# Main_Schematic.net
KiCad netlist of a schematic drawn in Altium Designer
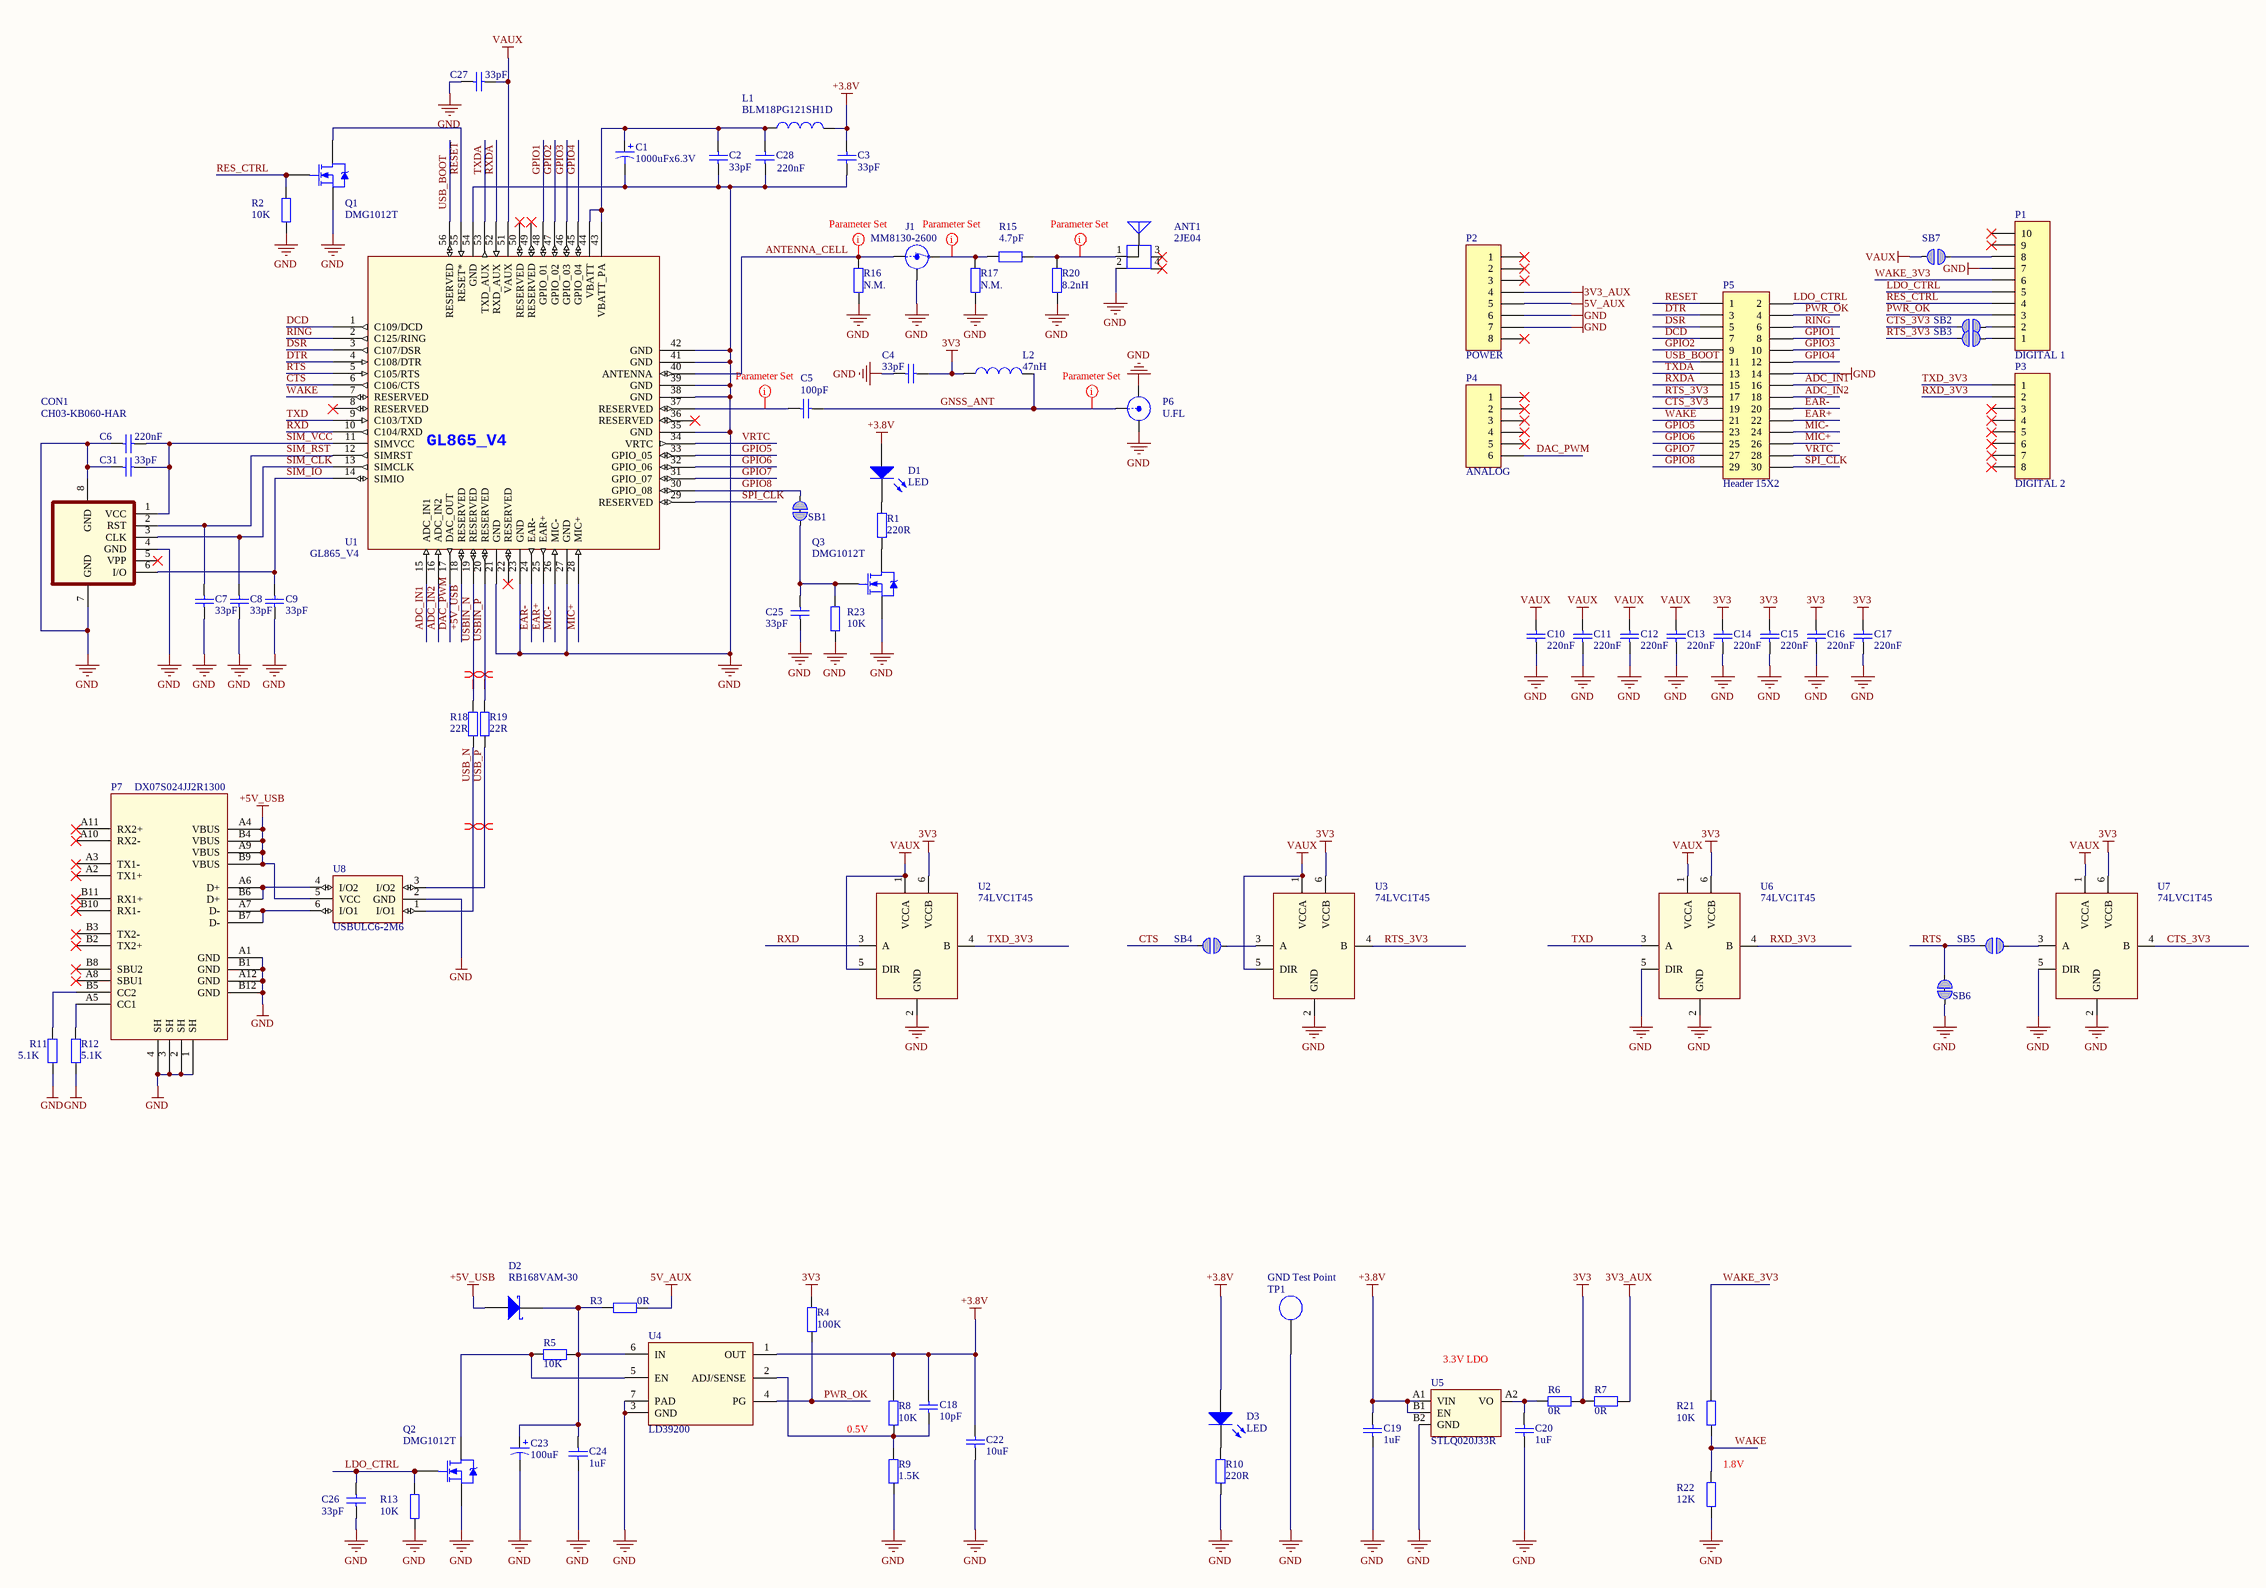
[diagram p0: Main Schematic.SchDoc]

(export (version "E")
  (design (tool "Eeschema 10.0.6"))
  (components
    (comp (ref "ANT1")
      (value "2JE04")
      (footprint "2JE04")
      (description "Generic Antenna")
      (fields (field (name "MANUFACTURER") "2J"))
      (libsource (lib "RUT_GE310_GNSS") (part "Antenna"))
    )
    (comp (ref "C1")
      (value "1000uFx6.3V")
      (footprint "7361-38")
      (fields
        (field (name "MANUFACTURER") "AVX")
        (field (name "MANUFACTURER PART NO.") "TPSV108M006R0050")
        (field (name "Comment") "electrolytic capacitor")
      )
      (libsource (lib "Miscellaneous Devices") (part "Cap Pol1"))
    )
    (comp (ref "C2")
      (value "33pF")
      (footprint "C0402")
      (description "Capacitor (Semiconductor SIM Model)")
      (fields (field (name "MANUFACTURER") "AVX") (field (name "MANUFACTURER PART NO.") "04025A330JAT2A"))
      (libsource (lib "Miscellaneous Devices") (part "Cap Semi"))
    )
    (comp (ref "C3")
      (value "33pF")
      (footprint "C0402")
      (description "Capacitor (Semiconductor SIM Model)")
      (fields (field (name "MANUFACTURER") "AVX") (field (name "MANUFACTURER PART NO.") "04025A330JAT2A"))
      (libsource (lib "Miscellaneous Devices") (part "Cap Semi"))
    )
    (comp (ref "C4")
      (value "33pF")
      (footprint "C0402")
      (description "Capacitor (Semiconductor SIM Model)")
      (fields (field (name "MANUFACTURER") "AVX") (field (name "MANUFACTURER PART NO.") "04025A330JAT2A"))
      (libsource (lib "Miscellaneous Devices") (part "Cap Semi"))
    )
    (comp (ref "C5")
      (value "100pF")
      (footprint "C0402")
      (description "Capacitor (Semiconductor SIM Model)")
      (fields
        (field (name "MANUFACTURER") "Samsung Electronics")
        (field (name "MANUFACTURER PART NO.") "CL05C101JB5NNNC")
      )
      (libsource (lib "Miscellaneous Devices") (part "Cap Semi"))
    )
    (comp (ref "C6")
      (value "220nF")
      (footprint "C0402")
      (description "Capacitor (Semiconductor SIM Model)")
      (fields
        (field (name "MANUFACTURER") "YAGEO")
        (field (name "MANUFACTURER PART NO.") "CC0402KRX5R5BB224")
      )
      (libsource (lib "Miscellaneous Devices") (part "Cap Semi"))
    )
    (comp (ref "C7")
      (value "33pF")
      (footprint "C0402")
      (description "Capacitor (Semiconductor SIM Model)")
      (fields (field (name "MANUFACTURER") "AVX") (field (name "MANUFACTURER PART NO.") "04025A330JAT2A"))
      (libsource (lib "Miscellaneous Devices") (part "Cap Semi"))
    )
    (comp (ref "C8")
      (value "33pF")
      (footprint "C0402")
      (description "Capacitor (Semiconductor SIM Model)")
      (fields (field (name "MANUFACTURER") "AVX") (field (name "MANUFACTURER PART NO.") "04025A330JAT2A"))
      (libsource (lib "Miscellaneous Devices") (part "Cap Semi"))
    )
    (comp (ref "C9")
      (value "33pF")
      (footprint "C0402")
      (description "Capacitor (Semiconductor SIM Model)")
      (fields (field (name "MANUFACTURER") "AVX") (field (name "MANUFACTURER PART NO.") "04025A330JAT2A"))
      (libsource (lib "Miscellaneous Devices") (part "Cap Semi"))
    )
    (comp (ref "C10")
      (value "220nF")
      (footprint "C0402")
      (description "Capacitor (Semiconductor SIM Model)")
      (fields
        (field (name "MANUFACTURER") "YAGEO")
        (field (name "MANUFACTURER PART NO.") "CC0402KRX5R5BB224")
      )
      (libsource (lib "Miscellaneous Devices") (part "Cap Semi"))
    )
    (comp (ref "C11")
      (value "220nF")
      (footprint "C0402")
      (description "Capacitor (Semiconductor SIM Model)")
      (fields
        (field (name "MANUFACTURER") "YAGEO")
        (field (name "MANUFACTURER PART NO.") "CC0402KRX5R5BB224")
      )
      (libsource (lib "Miscellaneous Devices") (part "Cap Semi"))
    )
    (comp (ref "C12")
      (value "220nF")
      (footprint "C0402")
      (description "Capacitor (Semiconductor SIM Model)")
      (fields
        (field (name "MANUFACTURER") "YAGEO")
        (field (name "MANUFACTURER PART NO.") "CC0402KRX5R5BB224")
      )
      (libsource (lib "Miscellaneous Devices") (part "Cap Semi"))
    )
    (comp (ref "C13")
      (value "220nF")
      (footprint "C0402")
      (description "Capacitor (Semiconductor SIM Model)")
      (fields
        (field (name "MANUFACTURER") "YAGEO")
        (field (name "MANUFACTURER PART NO.") "CC0402KRX5R5BB224")
      )
      (libsource (lib "Miscellaneous Devices") (part "Cap Semi"))
    )
    (comp (ref "C14")
      (value "220nF")
      (footprint "C0402")
      (description "Capacitor (Semiconductor SIM Model)")
      (fields
        (field (name "MANUFACTURER") "YAGEO")
        (field (name "MANUFACTURER PART NO.") "CC0402KRX5R5BB224")
      )
      (libsource (lib "Miscellaneous Devices") (part "Cap Semi"))
    )
    (comp (ref "C15")
      (value "220nF")
      (footprint "C0402")
      (description "Capacitor (Semiconductor SIM Model)")
      (fields
        (field (name "MANUFACTURER") "YAGEO")
        (field (name "MANUFACTURER PART NO.") "CC0402KRX5R5BB224")
      )
      (libsource (lib "Miscellaneous Devices") (part "Cap Semi"))
    )
    (comp (ref "C16")
      (value "220nF")
      (footprint "C0402")
      (description "Capacitor (Semiconductor SIM Model)")
      (fields
        (field (name "MANUFACTURER") "YAGEO")
        (field (name "MANUFACTURER PART NO.") "CC0402KRX5R5BB224")
      )
      (libsource (lib "Miscellaneous Devices") (part "Cap Semi"))
    )
    (comp (ref "C17")
      (value "220nF")
      (footprint "C0402")
      (description "Capacitor (Semiconductor SIM Model)")
      (fields
        (field (name "MANUFACTURER") "YAGEO")
        (field (name "MANUFACTURER PART NO.") "CC0402KRX5R5BB224")
      )
      (libsource (lib "Miscellaneous Devices") (part "Cap Semi"))
    )
    (comp (ref "C18")
      (value "10pF")
      (footprint "C0402")
      (description "Capacitor (Semiconductor SIM Model)")
      (fields
        (field (name "MANUFACTURER") "YAGEO")
        (field (name "MANUFACTURER PART NO.") "CC0402JRNPO9BN100")
      )
      (libsource (lib "Miscellaneous Devices") (part "Cap Semi"))
    )
    (comp (ref "C19")
      (value "1uF")
      (footprint "C0402")
      (description "Capacitor (Semiconductor SIM Model)")
      (fields
        (field (name "MANUFACTURER") "Samsung Electronics")
        (field (name "MANUFACTURER PART NO.") "CL05A225MQ5NNNC")
      )
      (libsource (lib "Miscellaneous Devices") (part "Cap Semi"))
    )
    (comp (ref "C20")
      (value "1uF")
      (footprint "C0402")
      (description "Capacitor (Semiconductor SIM Model)")
      (fields
        (field (name "MANUFACTURER") "Samsung Electronics")
        (field (name "MANUFACTURER PART NO.") "CL05A225MQ5NNNC")
      )
      (libsource (lib "Miscellaneous Devices") (part "Cap Semi"))
    )
    (comp (ref "C22")
      (value "10uF")
      (footprint "C0402")
      (description "Capacitor (Semiconductor SIM Model)")
      (fields
        (field (name "MANUFACTURER") "Samsung Electronics")
        (field (name "MANUFACTURER PART NO.") "CL05A106MP5NUNC")
      )
      (libsource (lib "Miscellaneous Devices") (part "Cap Semi"))
    )
    (comp (ref "C23")
      (value "100uF")
      (footprint "Case-B")
      (fields
        (field (name "MANUFACTURER") "AVX")
        (field (name "MANUFACTURER PART NO.") "TPSB107K006R0400")
        (field (name "Comment") "electrolytic capacitor")
      )
      (libsource (lib "Miscellaneous Devices") (part "Cap Pol1"))
    )
    (comp (ref "C24")
      (value "1uF")
      (footprint "C0402")
      (description "Capacitor (Semiconductor SIM Model)")
      (fields
        (field (name "MANUFACTURER") "Samsung Electronics")
        (field (name "MANUFACTURER PART NO.") "CL05A106MP5NUNC")
      )
      (libsource (lib "Miscellaneous Devices") (part "Cap Semi"))
    )
    (comp (ref "C25")
      (value "33pF")
      (footprint "C0402")
      (description "Capacitor (Semiconductor SIM Model)")
      (fields (field (name "MANUFACTURER") "AVX") (field (name "MANUFACTURER PART NO.") "04025A330JAT2A"))
      (libsource (lib "Miscellaneous Devices") (part "Cap Semi"))
    )
    (comp (ref "C26")
      (value "33pF")
      (footprint "C0402")
      (description "Capacitor (Semiconductor SIM Model)")
      (fields
        (field (name "MANUFACTURER") "YAGEO")
        (field (name "MANUFACTURER PART NO.") "CC0402JRNPO9BN100")
      )
      (libsource (lib "Miscellaneous Devices") (part "Cap Semi"))
    )
    (comp (ref "C27")
      (value "33pF")
      (footprint "C0402")
      (description "Capacitor (Semiconductor SIM Model)")
      (fields (field (name "MANUFACTURER") "AVX") (field (name "MANUFACTURER PART NO.") "04025A330JAT2A"))
      (libsource (lib "Miscellaneous Devices") (part "Cap Semi"))
    )
    (comp (ref "C28")
      (value "220nF")
      (footprint "C0402")
      (description "Capacitor (Semiconductor SIM Model)")
      (fields
        (field (name "MANUFACTURER") "YAGEO")
        (field (name "MANUFACTURER PART NO.") "CC0402KRX5R5BB224")
      )
      (libsource (lib "Miscellaneous Devices") (part "Cap Semi"))
    )
    (comp (ref "C31")
      (value "33pF")
      (footprint "C0402")
      (description "Capacitor (Semiconductor SIM Model)")
      (fields (field (name "MANUFACTURER") "AVX") (field (name "MANUFACTURER PART NO.") "04025A330JAT2A"))
      (libsource (lib "Miscellaneous Devices") (part "Cap Semi"))
    )
    (comp (ref "CON1")
      (value "CH03-KB060-HAR")
      (footprint "CH03-KB")
      (description "Nano SIM Card Connector")
      (fields (field (name "MANUFACTURER") "GradConn"))
      (libsource (lib "CH03-KB060-HAR") (part "CH03-KB060-HAR"))
    )
    (comp (ref "D1")
      (value "LED")
      (footprint "LED0805")
      (description "Typical SMD LED")
      (fields (field (name "MANUFACTURER") "LITE ON") (field (name "MANUFACTURER PART NO.") "LTST-C170KGKT"))
      (libsource (lib "Miscellaneous Devices") (part "LED2"))
    )
    (comp (ref "D2")
      (value "RB168VAM-30")
      (footprint "SOD323")
      (description "Schottky Diode")
      (fields (field (name "MANUFACTURER") "ROHM"))
      (libsource (lib "Miscellaneous Devices") (part "D Schottky"))
    )
    (comp (ref "D3")
      (value "LED")
      (footprint "LED0805")
      (description "Typical SMD LED")
      (fields (field (name "MANUFACTURER") "LITE ON") (field (name "MANUFACTURER PART NO.") "LTST-C170KGKT"))
      (libsource (lib "Miscellaneous Devices") (part "LED2"))
    )
    (comp (ref "J1")
      (value "MM8130-2600")
      (footprint "COAXIAL-SWF")
      (description "Coaxial Connector with Switch")
      (fields (field (name "MANUFACTURER") "Murata") (field (name "MANUFACTURER PART NO.") "MM8130-2600RB8"))
      (libsource (lib "Nordic Passive DB") (part "Coaxial-Internal-SW"))
    )
    (comp (ref "L1")
      (value "BLM18PG121SH1D")
      (footprint "L0603")
      (description "Inductor")
      (fields (field (name "MANUFACTURER") "muRata"))
      (libsource (lib "Miscellaneous Devices") (part "Inductor"))
    )
    (comp (ref "L2")
      (value "47nH")
      (footprint "L0402")
      (description "Inductor")
      (fields (field (name "MANUFACTURER") "muRata") (field (name "MANUFACTURER PART NO.") "LQW15AN47NJ00D"))
      (libsource (lib "Miscellaneous Devices") (part "Inductor"))
    )
    (comp (ref "P1")
      (value "DIGITAL 1")
      (footprint "HDR1X10")
      (fields
        (field (name "MANUFACTURER") "SparkFun Electronics")
        (field (name "MANUFACTURER PART NO.") "PRT-11417")
      )
      (libsource (lib "Miscellaneous Connectors") (part "Header 10"))
    )
    (comp (ref "P2") (value "POWER") (footprint "HDR1X8") (libsource (lib "") (part "Header 8_1")))
    (comp (ref "P3")
      (value "DIGITAL 2")
      (footprint "HDR1X8")
      (libsource (lib "Miscellaneous Connectors") (part "Header 8"))
    )
    (comp (ref "P4")
      (value "ANALOG")
      (footprint "HDR1X6")
      (libsource (lib "Miscellaneous Connectors") (part "Header 6"))
    )
    (comp (ref "P5")
      (value "Header 15X2")
      (footprint "HDR2X15")
      (description "Header, 15-Pin, Dual row")
      (libsource (lib "Miscellaneous Connectors") (part "Header 15X2"))
    )
    (comp (ref "P6")
      (value "U.FL")
      (footprint "U.FL_Connector_Male")
      (fields
        (field (name "MANUFACTURER") "HIROSE")
        (field (name "MANUFACTURER PART NO.") "U.FL-R-SMT-1(10)")
      )
      (libsource (lib "RUT_L865_Project_1") (part "SMB"))
    )
    (comp (ref "P7")
      (value "DX07S024JJ2R1300")
      (footprint "DX07_USB_C")
      (description "24P USB C DUAL SMT ON BOARD")
      (fields (field (name "MANUFACTURER") "JAE"))
      (libsource (lib "DX07S024JJ2R1300") (part "DX07S024JJ2R1300"))
    )
    (comp (ref "Q1")
      (value "DMG1012T")
      (footprint "SOT-523_custom")
      (description "N-Channel Power MOSFET")
      (fields (field (name "MANUFACTURER") "Diodes Inc.") (field (name "MANUFACTURER PART NO.") "DMG1012T-7"))
      (libsource (lib "Miscellaneous Devices") (part "NMOS-2"))
    )
    (comp (ref "Q2")
      (value "DMG1012T")
      (footprint "SOT-523_custom")
      (description "N-Channel Power MOSFET")
      (fields (field (name "MANUFACTURER") "Diodes Inc.") (field (name "MANUFACTURER PART NO.") "DMG1012T-7"))
      (libsource (lib "Miscellaneous Devices") (part "NMOS-2"))
    )
    (comp (ref "Q3")
      (value "DMG1012T")
      (footprint "SOT-523_custom")
      (description "N-Channel Power MOSFET")
      (fields (field (name "MANUFACTURER") "Diodes Inc.") (field (name "MANUFACTURER PART NO.") "DMG1012T-7"))
      (libsource (lib "Miscellaneous Devices") (part "NMOS-2"))
    )
    (comp (ref "R1")
      (value "220R")
      (footprint "R0402")
      (fields
        (field (name "MANUFACTURER") "ASJ")
        (field (name "MANUFACTURER PART NO.") "CR10-221-JK")
        (field (name "Comment") "Res2")
      )
      (libsource (lib "Miscellaneous Devices") (part "Res2"))
    )
    (comp (ref "R2")
      (value "10K")
      (footprint "R0402")
      (fields
        (field (name "MANUFACTURER") "ASJ")
        (field (name "MANUFACTURER PART NO.") "CR10-103-JK")
        (field (name "Comment") "Res2")
      )
      (libsource (lib "") (part "Res2_1"))
    )
    (comp (ref "R3")
      (value "0R")
      (footprint "R0402")
      (fields
        (field (name "MANUFACTURER") "YAGEO")
        (field (name "MANUFACTURER PART NO.") "RC0402FR-070RL")
        (field (name "Comment") "Res2")
      )
      (libsource (lib "") (part "Res2_2"))
    )
    (comp (ref "R4")
      (value "100K")
      (footprint "R0402")
      (fields
        (field (name "MANUFACTURER") "ASJ")
        (field (name "MANUFACTURER PART NO.") "CR10-104-JK")
        (field (name "Comment") "Res2")
      )
      (libsource (lib "") (part "Res2_1"))
    )
    (comp (ref "R5")
      (value "10K")
      (footprint "R0402")
      (fields
        (field (name "MANUFACTURER") "ASJ")
        (field (name "MANUFACTURER PART NO.") "CR10-103-JK")
        (field (name "Comment") "Res2")
      )
      (libsource (lib "") (part "Res2_3"))
    )
    (comp (ref "R6")
      (value "0R")
      (footprint "R0402")
      (fields
        (field (name "MANUFACTURER") "YAGEO")
        (field (name "MANUFACTURER PART NO.") "RC0402FR-070RL")
        (field (name "Comment") "Res2")
      )
      (libsource (lib "") (part "Res2_2"))
    )
    (comp (ref "R7")
      (value "0R")
      (footprint "R0402")
      (fields
        (field (name "MANUFACTURER") "YAGEO")
        (field (name "MANUFACTURER PART NO.") "RC0402FR-070RL")
        (field (name "Comment") "Res2")
      )
      (libsource (lib "") (part "Res2_2"))
    )
    (comp (ref "R8")
      (value "10K")
      (footprint "R0402")
      (fields
        (field (name "MANUFACTURER") "ASJ")
        (field (name "MANUFACTURER PART NO.") "CR10-103-JK")
        (field (name "Comment") "Res2")
      )
      (libsource (lib "Miscellaneous Devices") (part "Res2"))
    )
    (comp (ref "R9")
      (value "1.5K")
      (footprint "R0402")
      (fields
        (field (name "MANUFACTURER") "YAGEO")
        (field (name "MANUFACTURER PART NO.") "RC0402JR-071K5L")
        (field (name "Comment") "Res2")
      )
      (libsource (lib "Miscellaneous Devices") (part "Res2"))
    )
    (comp (ref "R10")
      (value "220R")
      (footprint "R0402")
      (fields
        (field (name "MANUFACTURER") "ASJ")
        (field (name "MANUFACTURER PART NO.") "CR10-221-JK")
        (field (name "Comment") "Res2")
      )
      (libsource (lib "Miscellaneous Devices") (part "Res2"))
    )
    (comp (ref "R11")
      (value "5.1K")
      (footprint "R0402")
      (fields
        (field (name "MANUFACTURER") "ASJ")
        (field (name "MANUFACTURER PART NO.") "CR10-103-JK")
        (field (name "Comment") "Res2")
      )
      (libsource (lib "") (part "Res2_3"))
    )
    (comp (ref "R12")
      (value "5.1K")
      (footprint "R0402")
      (fields
        (field (name "MANUFACTURER") "ASJ")
        (field (name "MANUFACTURER PART NO.") "CR10-103-JK")
        (field (name "Comment") "Res2")
      )
      (libsource (lib "") (part "Res2_3"))
    )
    (comp (ref "R13")
      (value "10K")
      (footprint "R0402")
      (fields
        (field (name "MANUFACTURER") "ASJ")
        (field (name "MANUFACTURER PART NO.") "CR10-103-JK")
        (field (name "Comment") "Res2")
      )
      (libsource (lib "") (part "Res2_1"))
    )
    (comp (ref "R15")
      (value "4.7pF")
      (footprint "R0402")
      (fields
        (field (name "MANUFACTURER") "Samsung Electronics")
        (field (name "MANUFACTURER PART NO.") "CL05C4R7BB5NNNC")
        (field (name "Comment") "Res2")
      )
      (libsource (lib "") (part "Res2_3"))
    )
    (comp (ref "R16")
      (value "N.M.")
      (footprint "R0402")
      (fields (field (name "Comment") "Res2"))
      (libsource (lib "Miscellaneous Devices") (part "Res2"))
    )
    (comp (ref "R17")
      (value "N.M.")
      (footprint "R0402")
      (fields (field (name "Comment") "Res2"))
      (libsource (lib "Miscellaneous Devices") (part "Res2"))
    )
    (comp (ref "R18")
      (value "22R")
      (footprint "R0402")
      (fields
        (field (name "MANUFACTURER") "ASJ")
        (field (name "MANUFACTURER PART NO.") "CR10-220-JK")
        (field (name "Comment") "Res2")
      )
      (libsource (lib "Miscellaneous Devices") (part "Res2"))
    )
    (comp (ref "R19")
      (value "22R")
      (footprint "R0402")
      (fields
        (field (name "MANUFACTURER") "ASJ")
        (field (name "MANUFACTURER PART NO.") "CR10-220-JK")
        (field (name "Comment") "Res2")
      )
      (libsource (lib "Miscellaneous Devices") (part "Res2"))
    )
    (comp (ref "R20")
      (value "8.2nH")
      (footprint "R0402")
      (fields
        (field (name "MANUFACTURER") "Samsung Electronics")
        (field (name "MANUFACTURER PART NO.") "CIH05T8N2JNC")
        (field (name "Comment") "Res2")
      )
      (libsource (lib "Miscellaneous Devices") (part "Res2"))
    )
    (comp (ref "R21")
      (value "10K")
      (footprint "R0402")
      (fields
        (field (name "MANUFACTURER") "ASJ")
        (field (name "MANUFACTURER PART NO.") "CR10-103-JK")
        (field (name "Comment") "Res2")
      )
      (libsource (lib "") (part "Res2_1"))
    )
    (comp (ref "R22")
      (value "12K")
      (footprint "R0402")
      (fields
        (field (name "MANUFACTURER") "ASJ")
        (field (name "MANUFACTURER PART NO.") "CR10-123-JK")
        (field (name "Comment") "Res2")
      )
      (libsource (lib "") (part "Res2_1"))
    )
    (comp (ref "R23")
      (value "10K")
      (footprint "R0402")
      (fields
        (field (name "MANUFACTURER") "ASJ")
        (field (name "MANUFACTURER PART NO.") "CR10-103-JK")
        (field (name "Comment") "Res2")
      )
      (libsource (lib "") (part "Res2_1"))
    )
    (comp (ref "SB1")
      (value "Solderbridge")
      (footprint "Solderbridge_Shorted")
      (libsource (lib "altium-import") (part "root_1_SOLDERBRIDGE_SHORTED_"))
    )
    (comp (ref "SB2")
      (value "Solderbridge")
      (footprint "Solderbridge")
      (libsource (lib "altium-import") (part "root_2_SOLDERBRIDGE_"))
    )
    (comp (ref "SB3")
      (value "Solderbridge")
      (footprint "Solderbridge")
      (libsource (lib "altium-import") (part "root_2_SOLDERBRIDGE_"))
    )
    (comp (ref "SB4")
      (value "Solderbridge")
      (footprint "Solderbridge")
      (libsource (lib "altium-import") (part "root_2_SOLDERBRIDGE_"))
    )
    (comp (ref "SB5")
      (value "Solderbridge")
      (footprint "Solderbridge")
      (libsource (lib "altium-import") (part "root_2_SOLDERBRIDGE_"))
    )
    (comp (ref "SB6")
      (value "Solderbridge")
      (footprint "Solderbridge_Shorted")
      (libsource (lib "altium-import") (part "root_1_SOLDERBRIDGE_SHORTED_"))
    )
    (comp (ref "SB7")
      (value "Solderbridge")
      (footprint "Solderbridge")
      (libsource (lib "altium-import") (part "root_2_SOLDERBRIDGE_"))
    )
    (comp (ref "TP1")
      (value "GND Test Point")
      (footprint "5019_keystone")
      (description "SMD Test Point")
      (fields
        (field (name "MANUFACTURER") "Keystone Electrincs")
        (field (name "MANUFACTURER PART NO.") "5019")
      )
      (libsource (lib "test_point") (part "5019"))
    )
    (comp (ref "U1")
      (value "GL865_V4")
      (footprint "GL865_V4")
      (fields
        (field (name "MANUFACTURER") "Telit")
        (field (name "MANUFACTURER PART NO.") "GL865Q4D401T001000")
      )
      (libsource (lib "GL865_V4") (part "GL865_V4"))
    )
    (comp (ref "U2")
      (value "74LVC1T45")
      (footprint "SOT23-6_custom")
      (fields
        (field (name "MANUFACTURER") "Diodes Inc.")
        (field (name "MANUFACTURER PART NO.") "74LVC1T45W6-7")
      )
      (libsource (lib "74LVC1T45") (part "74LVC1T45"))
    )
    (comp (ref "U3")
      (value "74LVC1T45")
      (footprint "SOT23-6_custom")
      (fields
        (field (name "MANUFACTURER") "Diodes Inc.")
        (field (name "MANUFACTURER PART NO.") "74LVC1T45W6-7")
      )
      (libsource (lib "74LVC1T45") (part "74LVC1T45"))
    )
    (comp (ref "U4")
      (value "LD39200")
      (footprint "DFN6")
      (description "2 A high PSRR ultra low drop linear regulator with reverse current protection")
      (fields
        (field (name "MANUFACTURER") "STMicroelectronics")
        (field (name "MANUFACTURER PART NO.") "LD39200PUR")
      )
      (libsource (lib "RUT2CLOUDPrjPcb") (part "LD39200"))
    )
    (comp (ref "U5")
      (value "STLQ020J33R")
      (footprint "Flip-Chip4")
      (description "LDO")
      (fields (field (name "MANUFACTURER") "STMicroelectronics"))
      (libsource (lib "RUTLEO") (part "STLQ020"))
    )
    (comp (ref "U6")
      (value "74LVC1T45")
      (footprint "SOT23-6_custom")
      (fields
        (field (name "MANUFACTURER") "Diodes Inc.")
        (field (name "MANUFACTURER PART NO.") "74LVC1T45W6-7")
      )
      (libsource (lib "74LVC1T45") (part "74LVC1T45"))
    )
    (comp (ref "U7")
      (value "74LVC1T45")
      (footprint "SOT23-6_custom")
      (fields
        (field (name "MANUFACTURER") "Diodes Inc.")
        (field (name "MANUFACTURER PART NO.") "74LVC1T45W6-7")
      )
      (libsource (lib "74LVC1T45") (part "74LVC1T45"))
    )
    (comp (ref "U8")
      (value "USBULC6-2M6")
      (footprint "Micro_QFN_6L")
      (description "Ultra large bandwidth ESD protection")
      (fields (field (name "MANUFACTURER") "STMicroelectronics"))
      (libsource (lib "USBULC6-2M6") (part "USBULC6-2M6"))
    )
  )
  (nets
    (net (code "1") (name "+3.8V") (class "Default")
      (node (ref "C18") (pin "2") (pinfunction "2_2") (pintype "passive"))
      (node (ref "C19") (pin "1") (pinfunction "1_1") (pintype "passive"))
      (node (ref "C22") (pin "2") (pinfunction "2_2") (pintype "passive"))
      (node (ref "C3") (pin "2") (pinfunction "2_2") (pintype "passive"))
      (node (ref "D1") (pin "1") (pinfunction "A_1") (pintype "passive"))
      (node (ref "D3") (pin "1") (pinfunction "A_1") (pintype "passive"))
      (node (ref "L1") (pin "2") (pinfunction "2_2") (pintype "passive"))
      (node (ref "R8") (pin "1") (pinfunction "1_1") (pintype "passive"))
      (node (ref "U4") (pin "1") (pinfunction "OUT_1") (pintype "passive"))
      (node (ref "U5") (pin "A1") (pinfunction "VIN_A1") (pintype "passive"))
      (node (ref "U5") (pin "B1") (pinfunction "EN_B1") (pintype "passive"))
    )
    (net (code "2") (name "+5V_USB") (class "Default")
      (node (ref "D2") (pin "1") (pinfunction "A_1") (pintype "passive"))
      (node (ref "P7") (pin "A4") (pinfunction "VBUS_A4") (pintype "passive"))
      (node (ref "P7") (pin "A9") (pinfunction "VBUS_A9") (pintype "passive"))
      (node (ref "P7") (pin "B4") (pinfunction "VBUS_B4") (pintype "passive"))
      (node (ref "P7") (pin "B9") (pinfunction "VBUS_B9") (pintype "passive"))
      (node (ref "U1") (pin "18") (pinfunction "RESERVED_18") (pintype "bidirectional"))
      (node (ref "U8") (pin "5") (pinfunction "VCC_5") (pintype "power_in"))
    )
    (net (code "3") (name "/ADC_IN1") (class "Default")
      (node (ref "P5") (pin "16") (pinfunction "16_16") (pintype "passive"))
      (node (ref "U1") (pin "15") (pinfunction "ADC_IN1_15") (pintype "input"))
    )
    (net (code "4") (name "/ADC_IN2") (class "Default")
      (node (ref "P5") (pin "18") (pinfunction "18_18") (pintype "passive"))
      (node (ref "U1") (pin "16") (pinfunction "ADC_IN2_16") (pintype "input"))
    )
    (net (code "5") (name "/ANTENNA_CELL") (class "Default")
      (node (ref "J1") (pin "1") (pinfunction "IN_1") (pintype "passive"))
      (node (ref "R16") (pin "1") (pinfunction "1_1") (pintype "passive"))
      (node (ref "U1") (pin "40") (pinfunction "ANTENNA_40") (pintype "bidirectional"))
    )
    (net (code "6") (name "/CTS") (class "Default")
      (node (ref "SB4") (pin "1") (pinfunction "0_1") (pintype "passive"))
      (node (ref "U1") (pin "6") (pinfunction "C106/CTS_6") (pintype "output"))
    )
    (net (code "7") (name "/CTS_3V3") (class "Default")
      (node (ref "P5") (pin "19") (pinfunction "19_19") (pintype "passive"))
      (node (ref "SB2") (pin "1") (pinfunction "0_1") (pintype "passive"))
      (node (ref "U7") (pin "4") (pinfunction "B_4") (pintype "passive"))
    )
    (net (code "8") (name "/DAC_PWM") (class "Default")
      (node (ref "P4") (pin "6") (pinfunction "6_6") (pintype "passive"))
      (node (ref "U1") (pin "17") (pinfunction "DAC_OUT_17") (pintype "output"))
    )
    (net (code "9") (name "/DCD") (class "Default")
      (node (ref "P5") (pin "7") (pinfunction "7_7") (pintype "passive"))
      (node (ref "U1") (pin "1") (pinfunction "C109/DCD_1") (pintype "output"))
    )
    (net (code "10") (name "/DSR") (class "Default")
      (node (ref "P5") (pin "5") (pinfunction "5_5") (pintype "passive"))
      (node (ref "U1") (pin "3") (pinfunction "C107/DSR_3") (pintype "output"))
    )
    (net (code "11") (name "/DTR") (class "Default")
      (node (ref "P5") (pin "3") (pinfunction "3_3") (pintype "passive"))
      (node (ref "U1") (pin "4") (pinfunction "C108/DTR_4") (pintype "input"))
    )
    (net (code "12") (name "/EAR+") (class "Default")
      (node (ref "P5") (pin "22") (pinfunction "22_22") (pintype "passive"))
      (node (ref "U1") (pin "25") (pinfunction "EAR+_25") (pintype "output"))
    )
    (net (code "13") (name "/EAR-") (class "Default")
      (node (ref "P5") (pin "20") (pinfunction "20_20") (pintype "passive"))
      (node (ref "U1") (pin "24") (pinfunction "EAR-_24") (pintype "output"))
    )
    (net (code "14") (name "/GNSS_ANT") (class "Default")
      (node (ref "C5") (pin "1") (pinfunction "1_1") (pintype "passive"))
      (node (ref "L2") (pin "2") (pinfunction "2_2") (pintype "passive"))
      (node (ref "P6") (pin "1") (pinfunction "X_1") (pintype "passive"))
    )
    (net (code "15") (name "/GPIO1") (class "Default")
      (node (ref "P5") (pin "8") (pinfunction "8_8") (pintype "passive"))
      (node (ref "U1") (pin "48") (pinfunction "GPIO_01_48") (pintype "bidirectional"))
    )
    (net (code "16") (name "/GPIO2") (class "Default")
      (node (ref "P5") (pin "9") (pinfunction "9_9") (pintype "passive"))
      (node (ref "U1") (pin "47") (pinfunction "GPIO_02_47") (pintype "bidirectional"))
    )
    (net (code "17") (name "/GPIO3") (class "Default")
      (node (ref "P5") (pin "10") (pinfunction "10_10") (pintype "passive"))
      (node (ref "U1") (pin "46") (pinfunction "GPIO_03_46") (pintype "bidirectional"))
    )
    (net (code "18") (name "/GPIO4") (class "Default")
      (node (ref "P5") (pin "12") (pinfunction "12_12") (pintype "passive"))
      (node (ref "U1") (pin "45") (pinfunction "GPIO_04_45") (pintype "bidirectional"))
    )
    (net (code "19") (name "/GPIO5") (class "Default")
      (node (ref "P5") (pin "23") (pinfunction "23_23") (pintype "passive"))
      (node (ref "U1") (pin "33") (pinfunction "GPIO_05_33") (pintype "bidirectional"))
    )
    (net (code "20") (name "/GPIO6") (class "Default")
      (node (ref "P5") (pin "25") (pinfunction "25_25") (pintype "passive"))
      (node (ref "U1") (pin "32") (pinfunction "GPIO_06_32") (pintype "bidirectional"))
    )
    (net (code "21") (name "/GPIO7") (class "Default")
      (node (ref "P5") (pin "27") (pinfunction "27_27") (pintype "passive"))
      (node (ref "U1") (pin "31") (pinfunction "GPIO_07_31") (pintype "bidirectional"))
    )
    (net (code "22") (name "/GPIO8") (class "Default")
      (node (ref "P5") (pin "29") (pinfunction "29_29") (pintype "passive"))
      (node (ref "SB1") (pin "1") (pinfunction "0_1") (pintype "passive"))
      (node (ref "U1") (pin "30") (pinfunction "GPIO_08_30") (pintype "bidirectional"))
    )
    (net (code "23") (name "/LDO_CTRL") (class "Default")
      (node (ref "C26") (pin "1") (pinfunction "1_1") (pintype "passive"))
      (node (ref "P1") (pin "5") (pinfunction "5_5") (pintype "passive"))
      (node (ref "P5") (pin "2") (pinfunction "2_2") (pintype "passive"))
      (node (ref "Q2") (pin "1") (pinfunction "G_1") (pintype "passive"))
      (node (ref "R13") (pin "2") (pinfunction "2_2") (pintype "passive"))
    )
    (net (code "24") (name "/MIC+") (class "Default")
      (node (ref "P5") (pin "26") (pinfunction "26_26") (pintype "passive"))
      (node (ref "U1") (pin "28") (pinfunction "MIC+_28") (pintype "input"))
    )
    (net (code "25") (name "/MIC-") (class "Default")
      (node (ref "P5") (pin "24") (pinfunction "24_24") (pintype "passive"))
      (node (ref "U1") (pin "26") (pinfunction "MIC-_26") (pintype "input"))
    )
    (net (code "26") (name "/PWR_OK") (class "Default")
      (node (ref "P1") (pin "3") (pinfunction "3_3") (pintype "passive"))
      (node (ref "P5") (pin "4") (pinfunction "4_4") (pintype "passive"))
      (node (ref "R4") (pin "1") (pinfunction "1_1") (pintype "passive"))
      (node (ref "U4") (pin "4") (pinfunction "PG_4") (pintype "passive"))
    )
    (net (code "27") (name "/RESET") (class "Default")
      (node (ref "P5") (pin "1") (pinfunction "1_1") (pintype "passive"))
      (node (ref "Q1") (pin "2") (pinfunction "D_2") (pintype "passive"))
      (node (ref "U1") (pin "55") (pinfunction "RESET*_55") (pintype "input"))
    )
    (net (code "28") (name "/RES_CTRL") (class "Default")
      (node (ref "P1") (pin "4") (pinfunction "4_4") (pintype "passive"))
      (node (ref "Q1") (pin "1") (pinfunction "G_1") (pintype "passive"))
      (node (ref "R2") (pin "2") (pinfunction "2_2") (pintype "passive"))
    )
    (net (code "29") (name "/RING") (class "Default")
      (node (ref "P5") (pin "6") (pinfunction "6_6") (pintype "passive"))
      (node (ref "U1") (pin "2") (pinfunction "C125/RING_2") (pintype "output"))
    )
    (net (code "30") (name "/RTS") (class "Default")
      (node (ref "SB5") (pin "1") (pinfunction "0_1") (pintype "passive"))
      (node (ref "SB6") (pin "1") (pinfunction "0_1") (pintype "passive"))
      (node (ref "U1") (pin "5") (pinfunction "C105/RTS_5") (pintype "input"))
    )
    (net (code "31") (name "/RTS_3V3") (class "Default")
      (node (ref "P5") (pin "17") (pinfunction "17_17") (pintype "passive"))
      (node (ref "SB3") (pin "1") (pinfunction "0_1") (pintype "passive"))
      (node (ref "U3") (pin "4") (pinfunction "B_4") (pintype "passive"))
    )
    (net (code "32") (name "/RXD") (class "Default")
      (node (ref "U1") (pin "10") (pinfunction "C104/RXD_10") (pintype "output"))
      (node (ref "U2") (pin "3") (pinfunction "A_3") (pintype "passive"))
    )
    (net (code "33") (name "/RXDA") (class "Default")
      (node (ref "P5") (pin "15") (pinfunction "15_15") (pintype "passive"))
      (node (ref "U1") (pin "52") (pinfunction "RXD_AUX_52") (pintype "input"))
    )
    (net (code "34") (name "/RXD_3V3") (class "Default")
      (node (ref "P3") (pin "2") (pinfunction "2_2") (pintype "passive"))
      (node (ref "U6") (pin "4") (pinfunction "B_4") (pintype "passive"))
    )
    (net (code "35") (name "/SIM_CLK") (class "Default")
      (node (ref "C8") (pin "1") (pinfunction "1_1") (pintype "passive"))
      (node (ref "CON1") (pin "3") (pinfunction "CLK_3") (pintype "passive"))
      (node (ref "U1") (pin "13") (pinfunction "SIMCLK_13") (pintype "output"))
    )
    (net (code "36") (name "/SIM_IO") (class "Default")
      (node (ref "C9") (pin "1") (pinfunction "1_1") (pintype "passive"))
      (node (ref "CON1") (pin "6") (pinfunction "I/O_6") (pintype "passive"))
      (node (ref "U1") (pin "14") (pinfunction "SIMIO_14") (pintype "bidirectional"))
    )
    (net (code "37") (name "/SIM_RST") (class "Default")
      (node (ref "C7") (pin "1") (pinfunction "1_1") (pintype "passive"))
      (node (ref "CON1") (pin "2") (pinfunction "RST_2") (pintype "passive"))
      (node (ref "U1") (pin "12") (pinfunction "SIMRST_12") (pintype "output"))
    )
    (net (code "38") (name "/SIM_VCC") (class "Default")
      (node (ref "C31") (pin "1") (pinfunction "1_1") (pintype "passive"))
      (node (ref "C6") (pin "1") (pinfunction "1_1") (pintype "passive"))
      (node (ref "CON1") (pin "1") (pinfunction "VCC_1") (pintype "passive"))
      (node (ref "U1") (pin "11") (pinfunction "SIMVCC_11") (pintype "power_in"))
    )
    (net (code "39") (name "/SPI_CLK") (class "Default")
      (node (ref "P5") (pin "30") (pinfunction "30_30") (pintype "passive"))
      (node (ref "U1") (pin "29") (pinfunction "RESERVED_29") (pintype "bidirectional"))
    )
    (net (code "40") (name "/TXD") (class "Default")
      (node (ref "U1") (pin "9") (pinfunction "C103/TXD_9") (pintype "input"))
      (node (ref "U6") (pin "3") (pinfunction "A_3") (pintype "passive"))
    )
    (net (code "41") (name "/TXDA") (class "Default")
      (node (ref "P5") (pin "13") (pinfunction "13_13") (pintype "passive"))
      (node (ref "U1") (pin "53") (pinfunction "TXD_AUX_53") (pintype "output"))
    )
    (net (code "42") (name "/TXD_3V3") (class "Default")
      (node (ref "P3") (pin "1") (pinfunction "1_1") (pintype "passive"))
      (node (ref "U2") (pin "4") (pinfunction "B_4") (pintype "passive"))
    )
    (net (code "43") (name "/USBIN_N") (class "Default")
      (node (ref "R18") (pin "1") (pinfunction "1_1") (pintype "passive"))
      (node (ref "U1") (pin "19") (pinfunction "RESERVED_19") (pintype "bidirectional"))
    )
    (net (code "44") (name "/USBIN_P") (class "Default")
      (node (ref "R19") (pin "1") (pinfunction "1_1") (pintype "passive"))
      (node (ref "U1") (pin "20") (pinfunction "RESERVED_20") (pintype "bidirectional"))
    )
    (net (code "45") (name "/USB_BOOT") (class "Default")
      (node (ref "P5") (pin "11") (pinfunction "11_11") (pintype "passive"))
      (node (ref "U1") (pin "56") (pinfunction "RESERVED_56") (pintype "bidirectional"))
    )
    (net (code "46") (name "/USB_N") (class "Default")
      (node (ref "R18") (pin "2") (pinfunction "2_2") (pintype "passive"))
      (node (ref "U8") (pin "1") (pinfunction "I/O1_1") (pintype "bidirectional"))
    )
    (net (code "47") (name "/USB_P") (class "Default")
      (node (ref "R19") (pin "2") (pinfunction "2_2") (pintype "passive"))
      (node (ref "U8") (pin "3") (pinfunction "I/O2_3") (pintype "bidirectional"))
    )
    (net (code "48") (name "/VRTC") (class "Default")
      (node (ref "P5") (pin "28") (pinfunction "28_28") (pintype "passive"))
      (node (ref "U1") (pin "34") (pinfunction "VRTC_34") (pintype "output"))
    )
    (net (code "49") (name "/WAKE") (class "Default")
      (node (ref "P5") (pin "21") (pinfunction "21_21") (pintype "passive"))
      (node (ref "R21") (pin "1") (pinfunction "1_1") (pintype "passive"))
      (node (ref "R22") (pin "2") (pinfunction "2_2") (pintype "passive"))
      (node (ref "U1") (pin "7") (pinfunction "RESERVED_7") (pintype "bidirectional"))
    )
    (net (code "50") (name "/WAKE_3V3") (class "Default")
      (node (ref "P1") (pin "6") (pinfunction "6_6") (pintype "passive"))
      (node (ref "R21") (pin "2") (pinfunction "2_2") (pintype "passive"))
    )
    (net (code "51") (name "3V3") (class "Default")
      (node (ref "C14") (pin "1") (pinfunction "1_1") (pintype "passive"))
      (node (ref "C15") (pin "1") (pinfunction "1_1") (pintype "passive"))
      (node (ref "C16") (pin "1") (pinfunction "1_1") (pintype "passive"))
      (node (ref "C17") (pin "1") (pinfunction "1_1") (pintype "passive"))
      (node (ref "C4") (pin "1") (pinfunction "1_1") (pintype "passive"))
      (node (ref "L2") (pin "1") (pinfunction "1_1") (pintype "passive"))
      (node (ref "R4") (pin "2") (pinfunction "2_2") (pintype "passive"))
      (node (ref "R6") (pin "1") (pinfunction "1_1") (pintype "passive"))
      (node (ref "R7") (pin "2") (pinfunction "2_2") (pintype "passive"))
      (node (ref "U2") (pin "6") (pinfunction "VCCB_6") (pintype "passive"))
      (node (ref "U3") (pin "6") (pinfunction "VCCB_6") (pintype "passive"))
      (node (ref "U6") (pin "6") (pinfunction "VCCB_6") (pintype "passive"))
      (node (ref "U7") (pin "6") (pinfunction "VCCB_6") (pintype "passive"))
    )
    (net (code "52") (name "3V3_AUX") (class "Default")
      (node (ref "P2") (pin "4") (pinfunction "4_4") (pintype "passive"))
      (node (ref "R7") (pin "1") (pinfunction "1_1") (pintype "passive"))
    )
    (net (code "53") (name "5V_AUX") (class "Default")
      (node (ref "P2") (pin "5") (pinfunction "5_5") (pintype "passive"))
      (node (ref "R3") (pin "1") (pinfunction "1_1") (pintype "passive"))
    )
    (net (code "54") (name "GND") (class "Default")
      (node (ref "ANT1") (pin "2") (pinfunction "2_2") (pintype "passive"))
      (node (ref "C1") (pin "2") (pinfunction "2_2") (pintype "passive"))
      (node (ref "C10") (pin "2") (pinfunction "2_2") (pintype "passive"))
      (node (ref "C11") (pin "2") (pinfunction "2_2") (pintype "passive"))
      (node (ref "C12") (pin "2") (pinfunction "2_2") (pintype "passive"))
      (node (ref "C13") (pin "2") (pinfunction "2_2") (pintype "passive"))
      (node (ref "C14") (pin "2") (pinfunction "2_2") (pintype "passive"))
      (node (ref "C15") (pin "2") (pinfunction "2_2") (pintype "passive"))
      (node (ref "C16") (pin "2") (pinfunction "2_2") (pintype "passive"))
      (node (ref "C17") (pin "2") (pinfunction "2_2") (pintype "passive"))
      (node (ref "C19") (pin "2") (pinfunction "2_2") (pintype "passive"))
      (node (ref "C2") (pin "1") (pinfunction "1_1") (pintype "passive"))
      (node (ref "C20") (pin "2") (pinfunction "2_2") (pintype "passive"))
      (node (ref "C22") (pin "1") (pinfunction "1_1") (pintype "passive"))
      (node (ref "C23") (pin "2") (pinfunction "2_2") (pintype "passive"))
      (node (ref "C24") (pin "1") (pinfunction "1_1") (pintype "passive"))
      (node (ref "C25") (pin "2") (pinfunction "2_2") (pintype "passive"))
      (node (ref "C26") (pin "2") (pinfunction "2_2") (pintype "passive"))
      (node (ref "C27") (pin "2") (pinfunction "2_2") (pintype "passive"))
      (node (ref "C28") (pin "2") (pinfunction "2_2") (pintype "passive"))
      (node (ref "C3") (pin "1") (pinfunction "1_1") (pintype "passive"))
      (node (ref "C31") (pin "2") (pinfunction "2_2") (pintype "passive"))
      (node (ref "C4") (pin "2") (pinfunction "2_2") (pintype "passive"))
      (node (ref "C6") (pin "2") (pinfunction "2_2") (pintype "passive"))
      (node (ref "C7") (pin "2") (pinfunction "2_2") (pintype "passive"))
      (node (ref "C8") (pin "2") (pinfunction "2_2") (pintype "passive"))
      (node (ref "C9") (pin "2") (pinfunction "2_2") (pintype "passive"))
      (node (ref "CON1") (pin "4") (pinfunction "GND_4") (pintype "passive"))
      (node (ref "CON1") (pin "7") (pinfunction "GND_7") (pintype "passive"))
      (node (ref "CON1") (pin "8") (pinfunction "GND_8") (pintype "passive"))
      (node (ref "J1") (pin "2") (pinfunction "Shield_2") (pintype "passive"))
      (node (ref "P1") (pin "7") (pinfunction "7_7") (pintype "passive"))
      (node (ref "P2") (pin "6") (pinfunction "6_6") (pintype "passive"))
      (node (ref "P2") (pin "7") (pinfunction "7_7") (pintype "passive"))
      (node (ref "P5") (pin "14") (pinfunction "14_14") (pintype "passive"))
      (node (ref "P6") (pin "2") (pinfunction "Y_2") (pintype "passive"))
      (node (ref "P6") (pin "3") (pinfunction "Y_3") (pintype "passive"))
      (node (ref "P7") (pin "1") (pinfunction "SH_1") (pintype "passive"))
      (node (ref "P7") (pin "2") (pinfunction "SH_2") (pintype "passive"))
      (node (ref "P7") (pin "3") (pinfunction "SH_3") (pintype "passive"))
      (node (ref "P7") (pin "4") (pinfunction "SH_4") (pintype "passive"))
      (node (ref "P7") (pin "A1") (pinfunction "GND_A1") (pintype "passive"))
      (node (ref "P7") (pin "A12") (pinfunction "GND_A12") (pintype "passive"))
      (node (ref "P7") (pin "B1") (pinfunction "GND_B1") (pintype "passive"))
      (node (ref "P7") (pin "B12") (pinfunction "GND_B12") (pintype "passive"))
      (node (ref "Q1") (pin "3") (pinfunction "S_3") (pintype "passive"))
      (node (ref "Q2") (pin "3") (pinfunction "S_3") (pintype "passive"))
      (node (ref "Q3") (pin "3") (pinfunction "S_3") (pintype "passive"))
      (node (ref "R10") (pin "2") (pinfunction "2_2") (pintype "passive"))
      (node (ref "R11") (pin "1") (pinfunction "1_1") (pintype "passive"))
      (node (ref "R12") (pin "1") (pinfunction "1_1") (pintype "passive"))
      (node (ref "R13") (pin "1") (pinfunction "1_1") (pintype "passive"))
      (node (ref "R16") (pin "2") (pinfunction "2_2") (pintype "passive"))
      (node (ref "R17") (pin "2") (pinfunction "2_2") (pintype "passive"))
      (node (ref "R2") (pin "1") (pinfunction "1_1") (pintype "passive"))
      (node (ref "R20") (pin "2") (pinfunction "2_2") (pintype "passive"))
      (node (ref "R22") (pin "1") (pinfunction "1_1") (pintype "passive"))
      (node (ref "R23") (pin "1") (pinfunction "1_1") (pintype "passive"))
      (node (ref "R9") (pin "2") (pinfunction "2_2") (pintype "passive"))
      (node (ref "SB6") (pin "2") (pinfunction "1_2") (pintype "passive"))
      (node (ref "TP1") (pin "1") (pinfunction "1_1") (pintype "passive"))
      (node (ref "U1") (pin "21") (pinfunction "GND_21") (pintype "power_in"))
      (node (ref "U1") (pin "23") (pinfunction "GND_23") (pintype "power_in"))
      (node (ref "U1") (pin "27") (pinfunction "GND_27") (pintype "power_in"))
      (node (ref "U1") (pin "35") (pinfunction "GND_35") (pintype "power_in"))
      (node (ref "U1") (pin "38") (pinfunction "GND_38") (pintype "power_in"))
      (node (ref "U1") (pin "39") (pinfunction "GND_39") (pintype "power_in"))
      (node (ref "U1") (pin "41") (pinfunction "GND_41") (pintype "power_in"))
      (node (ref "U1") (pin "42") (pinfunction "GND_42") (pintype "power_in"))
      (node (ref "U1") (pin "54") (pinfunction "GND_54") (pintype "power_in"))
      (node (ref "U2") (pin "2") (pinfunction "GND_2") (pintype "passive"))
      (node (ref "U3") (pin "2") (pinfunction "GND_2") (pintype "passive"))
      (node (ref "U4") (pin "3") (pinfunction "GND_3") (pintype "passive"))
      (node (ref "U4") (pin "7") (pinfunction "PAD_7") (pintype "passive"))
      (node (ref "U5") (pin "B2") (pinfunction "GND_B2") (pintype "passive"))
      (node (ref "U6") (pin "2") (pinfunction "GND_2") (pintype "passive"))
      (node (ref "U6") (pin "5") (pinfunction "DIR_5") (pintype "passive"))
      (node (ref "U7") (pin "2") (pinfunction "GND_2") (pintype "passive"))
      (node (ref "U7") (pin "5") (pinfunction "DIR_5") (pintype "passive"))
      (node (ref "U8") (pin "2") (pinfunction "GND_2") (pintype "power_in"))
    )
    (net (code "55") (name "Net-(ANT1-Pad1)") (class "Default")
      (node (ref "ANT1") (pin "1") (pinfunction "1_1") (pintype "passive"))
      (node (ref "R15") (pin "2") (pinfunction "2_2") (pintype "passive"))
      (node (ref "R20") (pin "1") (pinfunction "1_1") (pintype "passive"))
    )
    (net (code "56") (name "Net-(C5-Pad2)") (class "Default")
      (node (ref "C5") (pin "2") (pinfunction "2_2") (pintype "passive"))
      (node (ref "U1") (pin "37") (pinfunction "RESERVED_37") (pintype "bidirectional"))
    )
    (net (code "57") (name "Net-(D1-K)") (class "Default")
      (node (ref "D1") (pin "2") (pinfunction "K_2") (pintype "passive"))
      (node (ref "R1") (pin "1") (pinfunction "1_1") (pintype "passive"))
    )
    (net (code "58") (name "Net-(D2-K)") (class "Default")
      (node (ref "C23") (pin "1") (pinfunction "1_1") (pintype "passive"))
      (node (ref "C24") (pin "2") (pinfunction "2_2") (pintype "passive"))
      (node (ref "D2") (pin "2") (pinfunction "K_2") (pintype "passive"))
      (node (ref "R3") (pin "2") (pinfunction "2_2") (pintype "passive"))
      (node (ref "R5") (pin "2") (pinfunction "2_2") (pintype "passive"))
      (node (ref "U4") (pin "6") (pinfunction "IN_6") (pintype "passive"))
    )
    (net (code "59") (name "Net-(D3-K)") (class "Default")
      (node (ref "D3") (pin "2") (pinfunction "K_2") (pintype "passive"))
      (node (ref "R10") (pin "1") (pinfunction "1_1") (pintype "passive"))
    )
    (net (code "60") (name "Net-(J1-OUT)") (class "Default")
      (node (ref "J1") (pin "3") (pinfunction "OUT_3") (pintype "passive"))
      (node (ref "R15") (pin "1") (pinfunction "1_1") (pintype "passive"))
      (node (ref "R17") (pin "1") (pinfunction "1_1") (pintype "passive"))
    )
    (net (code "61") (name "Net-(P7-CC1)") (class "Default")
      (node (ref "P7") (pin "A5") (pinfunction "CC1_A5") (pintype "passive"))
      (node (ref "R12") (pin "2") (pinfunction "2_2") (pintype "passive"))
    )
    (net (code "62") (name "Net-(P7-CC2)") (class "Default")
      (node (ref "P7") (pin "B5") (pinfunction "CC2_B5") (pintype "passive"))
      (node (ref "R11") (pin "2") (pinfunction "2_2") (pintype "passive"))
    )
    (net (code "63") (name "Net-(P7-D+-PadA6)") (class "Default")
      (node (ref "P7") (pin "A6") (pinfunction "D+_A6") (pintype "passive"))
      (node (ref "P7") (pin "B6") (pinfunction "D+_B6") (pintype "passive"))
      (node (ref "U8") (pin "4") (pinfunction "I/O2_4") (pintype "bidirectional"))
    )
    (net (code "64") (name "Net-(P7-D--PadA7)") (class "Default")
      (node (ref "P7") (pin "A7") (pinfunction "D-_A7") (pintype "passive"))
      (node (ref "P7") (pin "B7") (pinfunction "D-_B7") (pintype "passive"))
      (node (ref "U8") (pin "6") (pinfunction "I/O1_6") (pintype "bidirectional"))
    )
    (net (code "65") (name "Net-(Q2-D)") (class "Default")
      (node (ref "Q2") (pin "2") (pinfunction "D_2") (pintype "passive"))
      (node (ref "R5") (pin "1") (pinfunction "1_1") (pintype "passive"))
      (node (ref "U4") (pin "5") (pinfunction "EN_5") (pintype "passive"))
    )
    (net (code "66") (name "Net-(Q3-D)") (class "Default")
      (node (ref "Q3") (pin "2") (pinfunction "D_2") (pintype "passive"))
      (node (ref "R1") (pin "2") (pinfunction "2_2") (pintype "passive"))
    )
    (net (code "67") (name "Net-(Q3-G)") (class "Default")
      (node (ref "C25") (pin "1") (pinfunction "1_1") (pintype "passive"))
      (node (ref "Q3") (pin "1") (pinfunction "G_1") (pintype "passive"))
      (node (ref "R23") (pin "2") (pinfunction "2_2") (pintype "passive"))
      (node (ref "SB1") (pin "2") (pinfunction "1_2") (pintype "passive"))
    )
    (net (code "68") (name "Net-(SB2-1)") (class "Default")
      (node (ref "P1") (pin "2") (pinfunction "2_2") (pintype "passive"))
      (node (ref "SB2") (pin "2") (pinfunction "1_2") (pintype "passive"))
    )
    (net (code "69") (name "Net-(SB3-1)") (class "Default")
      (node (ref "P1") (pin "1") (pinfunction "1_1") (pintype "passive"))
      (node (ref "SB3") (pin "2") (pinfunction "1_2") (pintype "passive"))
    )
    (net (code "70") (name "Net-(SB4-1)") (class "Default")
      (node (ref "SB4") (pin "2") (pinfunction "1_2") (pintype "passive"))
      (node (ref "U3") (pin "3") (pinfunction "A_3") (pintype "passive"))
    )
    (net (code "71") (name "Net-(SB5-1)") (class "Default")
      (node (ref "SB5") (pin "2") (pinfunction "1_2") (pintype "passive"))
      (node (ref "U7") (pin "3") (pinfunction "A_3") (pintype "passive"))
    )
    (net (code "72") (name "Net-(SB7-1)") (class "Default")
      (node (ref "P1") (pin "8") (pinfunction "8_8") (pintype "passive"))
      (node (ref "SB7") (pin "2") (pinfunction "1_2") (pintype "passive"))
    )
    (net (code "73") (name "Net-(U1-VBATT)") (class "Default")
      (node (ref "C1") (pin "1") (pinfunction "1_1") (pintype "passive"))
      (node (ref "C2") (pin "2") (pinfunction "2_2") (pintype "passive"))
      (node (ref "C28") (pin "1") (pinfunction "1_1") (pintype "passive"))
      (node (ref "L1") (pin "1") (pinfunction "1_1") (pintype "passive"))
      (node (ref "U1") (pin "43") (pinfunction "VBATT_PA_43") (pintype "power_in"))
      (node (ref "U1") (pin "44") (pinfunction "VBATT_44") (pintype "power_in"))
    )
    (net (code "74") (name "Net-(U4-ADJ{slash}SENSE)") (class "Default")
      (node (ref "C18") (pin "1") (pinfunction "1_1") (pintype "passive"))
      (node (ref "R8") (pin "2") (pinfunction "2_2") (pintype "passive"))
      (node (ref "R9") (pin "1") (pinfunction "1_1") (pintype "passive"))
      (node (ref "U4") (pin "2") (pinfunction "ADJ/SENSE_2") (pintype "passive"))
    )
    (net (code "75") (name "Net-(U5-VO)") (class "Default")
      (node (ref "C20") (pin "1") (pinfunction "1_1") (pintype "passive"))
      (node (ref "R6") (pin "2") (pinfunction "2_2") (pintype "passive"))
      (node (ref "U5") (pin "A2") (pinfunction "VO_A2") (pintype "passive"))
    )
    (net (code "76") (name "VAUX") (class "Default")
      (node (ref "C10") (pin "1") (pinfunction "1_1") (pintype "passive"))
      (node (ref "C11") (pin "1") (pinfunction "1_1") (pintype "passive"))
      (node (ref "C12") (pin "1") (pinfunction "1_1") (pintype "passive"))
      (node (ref "C13") (pin "1") (pinfunction "1_1") (pintype "passive"))
      (node (ref "C27") (pin "1") (pinfunction "1_1") (pintype "passive"))
      (node (ref "SB7") (pin "1") (pinfunction "0_1") (pintype "passive"))
      (node (ref "U1") (pin "51") (pinfunction "VAUX_51") (pintype "power_in"))
      (node (ref "U2") (pin "1") (pinfunction "VCCA_1") (pintype "passive"))
      (node (ref "U2") (pin "5") (pinfunction "DIR_5") (pintype "passive"))
      (node (ref "U3") (pin "1") (pinfunction "VCCA_1") (pintype "passive"))
      (node (ref "U3") (pin "5") (pinfunction "DIR_5") (pintype "passive"))
      (node (ref "U6") (pin "1") (pinfunction "VCCA_1") (pintype "passive"))
      (node (ref "U7") (pin "1") (pinfunction "VCCA_1") (pintype "passive"))
    )
    (net (code "77") (name "unconnected-(ANT1-Pad3)") (class "Default")
      (node (ref "ANT1") (pin "3") (pinfunction "3_3") (pintype "passive+no_connect"))
    )
    (net (code "78") (name "unconnected-(ANT1-Pad4)") (class "Default")
      (node (ref "ANT1") (pin "4") (pinfunction "4_4") (pintype "passive+no_connect"))
    )
    (net (code "79") (name "unconnected-(CON1-VPP-Pad5)") (class "Default")
      (node (ref "CON1") (pin "5") (pinfunction "VPP_5") (pintype "passive+no_connect"))
    )
    (net (code "80") (name "unconnected-(P1-Pad9)") (class "Default")
      (node (ref "P1") (pin "9") (pinfunction "9_9") (pintype "passive+no_connect"))
    )
    (net (code "81") (name "unconnected-(P1-Pad10)") (class "Default")
      (node (ref "P1") (pin "10") (pinfunction "10_10") (pintype "passive+no_connect"))
    )
    (net (code "82") (name "unconnected-(P2-Pad1)") (class "Default")
      (node (ref "P2") (pin "1") (pinfunction "1_1") (pintype "passive+no_connect"))
    )
    (net (code "83") (name "unconnected-(P2-Pad2)") (class "Default")
      (node (ref "P2") (pin "2") (pinfunction "2_2") (pintype "passive+no_connect"))
    )
    (net (code "84") (name "unconnected-(P2-Pad3)") (class "Default")
      (node (ref "P2") (pin "3") (pinfunction "3_3") (pintype "passive+no_connect"))
    )
    (net (code "85") (name "unconnected-(P2-Pad8)") (class "Default")
      (node (ref "P2") (pin "8") (pinfunction "8_8") (pintype "passive+no_connect"))
    )
    (net (code "86") (name "unconnected-(P3-Pad3)") (class "Default")
      (node (ref "P3") (pin "3") (pinfunction "3_3") (pintype "passive+no_connect"))
    )
    (net (code "87") (name "unconnected-(P3-Pad4)") (class "Default")
      (node (ref "P3") (pin "4") (pinfunction "4_4") (pintype "passive+no_connect"))
    )
    (net (code "88") (name "unconnected-(P3-Pad5)") (class "Default")
      (node (ref "P3") (pin "5") (pinfunction "5_5") (pintype "passive+no_connect"))
    )
    (net (code "89") (name "unconnected-(P3-Pad6)") (class "Default")
      (node (ref "P3") (pin "6") (pinfunction "6_6") (pintype "passive+no_connect"))
    )
    (net (code "90") (name "unconnected-(P3-Pad7)") (class "Default")
      (node (ref "P3") (pin "7") (pinfunction "7_7") (pintype "passive+no_connect"))
    )
    (net (code "91") (name "unconnected-(P3-Pad8)") (class "Default")
      (node (ref "P3") (pin "8") (pinfunction "8_8") (pintype "passive+no_connect"))
    )
    (net (code "92") (name "unconnected-(P4-Pad1)") (class "Default")
      (node (ref "P4") (pin "1") (pinfunction "1_1") (pintype "passive+no_connect"))
    )
    (net (code "93") (name "unconnected-(P4-Pad2)") (class "Default")
      (node (ref "P4") (pin "2") (pinfunction "2_2") (pintype "passive+no_connect"))
    )
    (net (code "94") (name "unconnected-(P4-Pad3)") (class "Default")
      (node (ref "P4") (pin "3") (pinfunction "3_3") (pintype "passive+no_connect"))
    )
    (net (code "95") (name "unconnected-(P4-Pad4)") (class "Default")
      (node (ref "P4") (pin "4") (pinfunction "4_4") (pintype "passive+no_connect"))
    )
    (net (code "96") (name "unconnected-(P4-Pad5)") (class "Default")
      (node (ref "P4") (pin "5") (pinfunction "5_5") (pintype "passive+no_connect"))
    )
    (net (code "97") (name "unconnected-(P7-RX1+-PadB11)") (class "Default")
      (node (ref "P7") (pin "B11") (pinfunction "RX1+_B11") (pintype "passive+no_connect"))
    )
    (net (code "98") (name "unconnected-(P7-RX1--PadB10)") (class "Default")
      (node (ref "P7") (pin "B10") (pinfunction "RX1-_B10") (pintype "passive+no_connect"))
    )
    (net (code "99") (name "unconnected-(P7-RX2+-PadA11)") (class "Default")
      (node (ref "P7") (pin "A11") (pinfunction "RX2+_A11") (pintype "passive+no_connect"))
    )
    (net (code "100") (name "unconnected-(P7-RX2--PadA10)") (class "Default")
      (node (ref "P7") (pin "A10") (pinfunction "RX2-_A10") (pintype "passive+no_connect"))
    )
    (net (code "101") (name "unconnected-(P7-SBU1-PadA8)") (class "Default")
      (node (ref "P7") (pin "A8") (pinfunction "SBU1_A8") (pintype "passive+no_connect"))
    )
    (net (code "102") (name "unconnected-(P7-SBU2-PadB8)") (class "Default")
      (node (ref "P7") (pin "B8") (pinfunction "SBU2_B8") (pintype "passive+no_connect"))
    )
    (net (code "103") (name "unconnected-(P7-TX1+-PadA2)") (class "Default")
      (node (ref "P7") (pin "A2") (pinfunction "TX1+_A2") (pintype "passive+no_connect"))
    )
    (net (code "104") (name "unconnected-(P7-TX1--PadA3)") (class "Default")
      (node (ref "P7") (pin "A3") (pinfunction "TX1-_A3") (pintype "passive+no_connect"))
    )
    (net (code "105") (name "unconnected-(P7-TX2+-PadB2)") (class "Default")
      (node (ref "P7") (pin "B2") (pinfunction "TX2+_B2") (pintype "passive+no_connect"))
    )
    (net (code "106") (name "unconnected-(P7-TX2--PadB3)") (class "Default")
      (node (ref "P7") (pin "B3") (pinfunction "TX2-_B3") (pintype "passive+no_connect"))
    )
    (net (code "107") (name "unconnected-(U1-RESERVED-Pad8)") (class "Default")
      (node (ref "U1") (pin "8") (pinfunction "RESERVED_8") (pintype "bidirectional+no_connect"))
    )
    (net (code "108") (name "unconnected-(U1-RESERVED-Pad22)") (class "Default")
      (node (ref "U1") (pin "22") (pinfunction "RESERVED_22") (pintype "bidirectional+no_connect"))
    )
    (net (code "109") (name "unconnected-(U1-RESERVED-Pad36)") (class "Default")
      (node (ref "U1") (pin "36") (pinfunction "RESERVED_36") (pintype "bidirectional+no_connect"))
    )
    (net (code "110") (name "unconnected-(U1-RESERVED-Pad49)") (class "Default")
      (node (ref "U1") (pin "49") (pinfunction "RESERVED_49") (pintype "bidirectional+no_connect"))
    )
    (net (code "111") (name "unconnected-(U1-RESERVED-Pad50)") (class "Default")
      (node (ref "U1") (pin "50") (pinfunction "RESERVED_50") (pintype "bidirectional+no_connect"))
    )
  )
)
